# S7CAS-PLEIADES-CARTE-MERE_P02_DDR3.net
KiCad netlist of a schematic drawn in Altium Designer
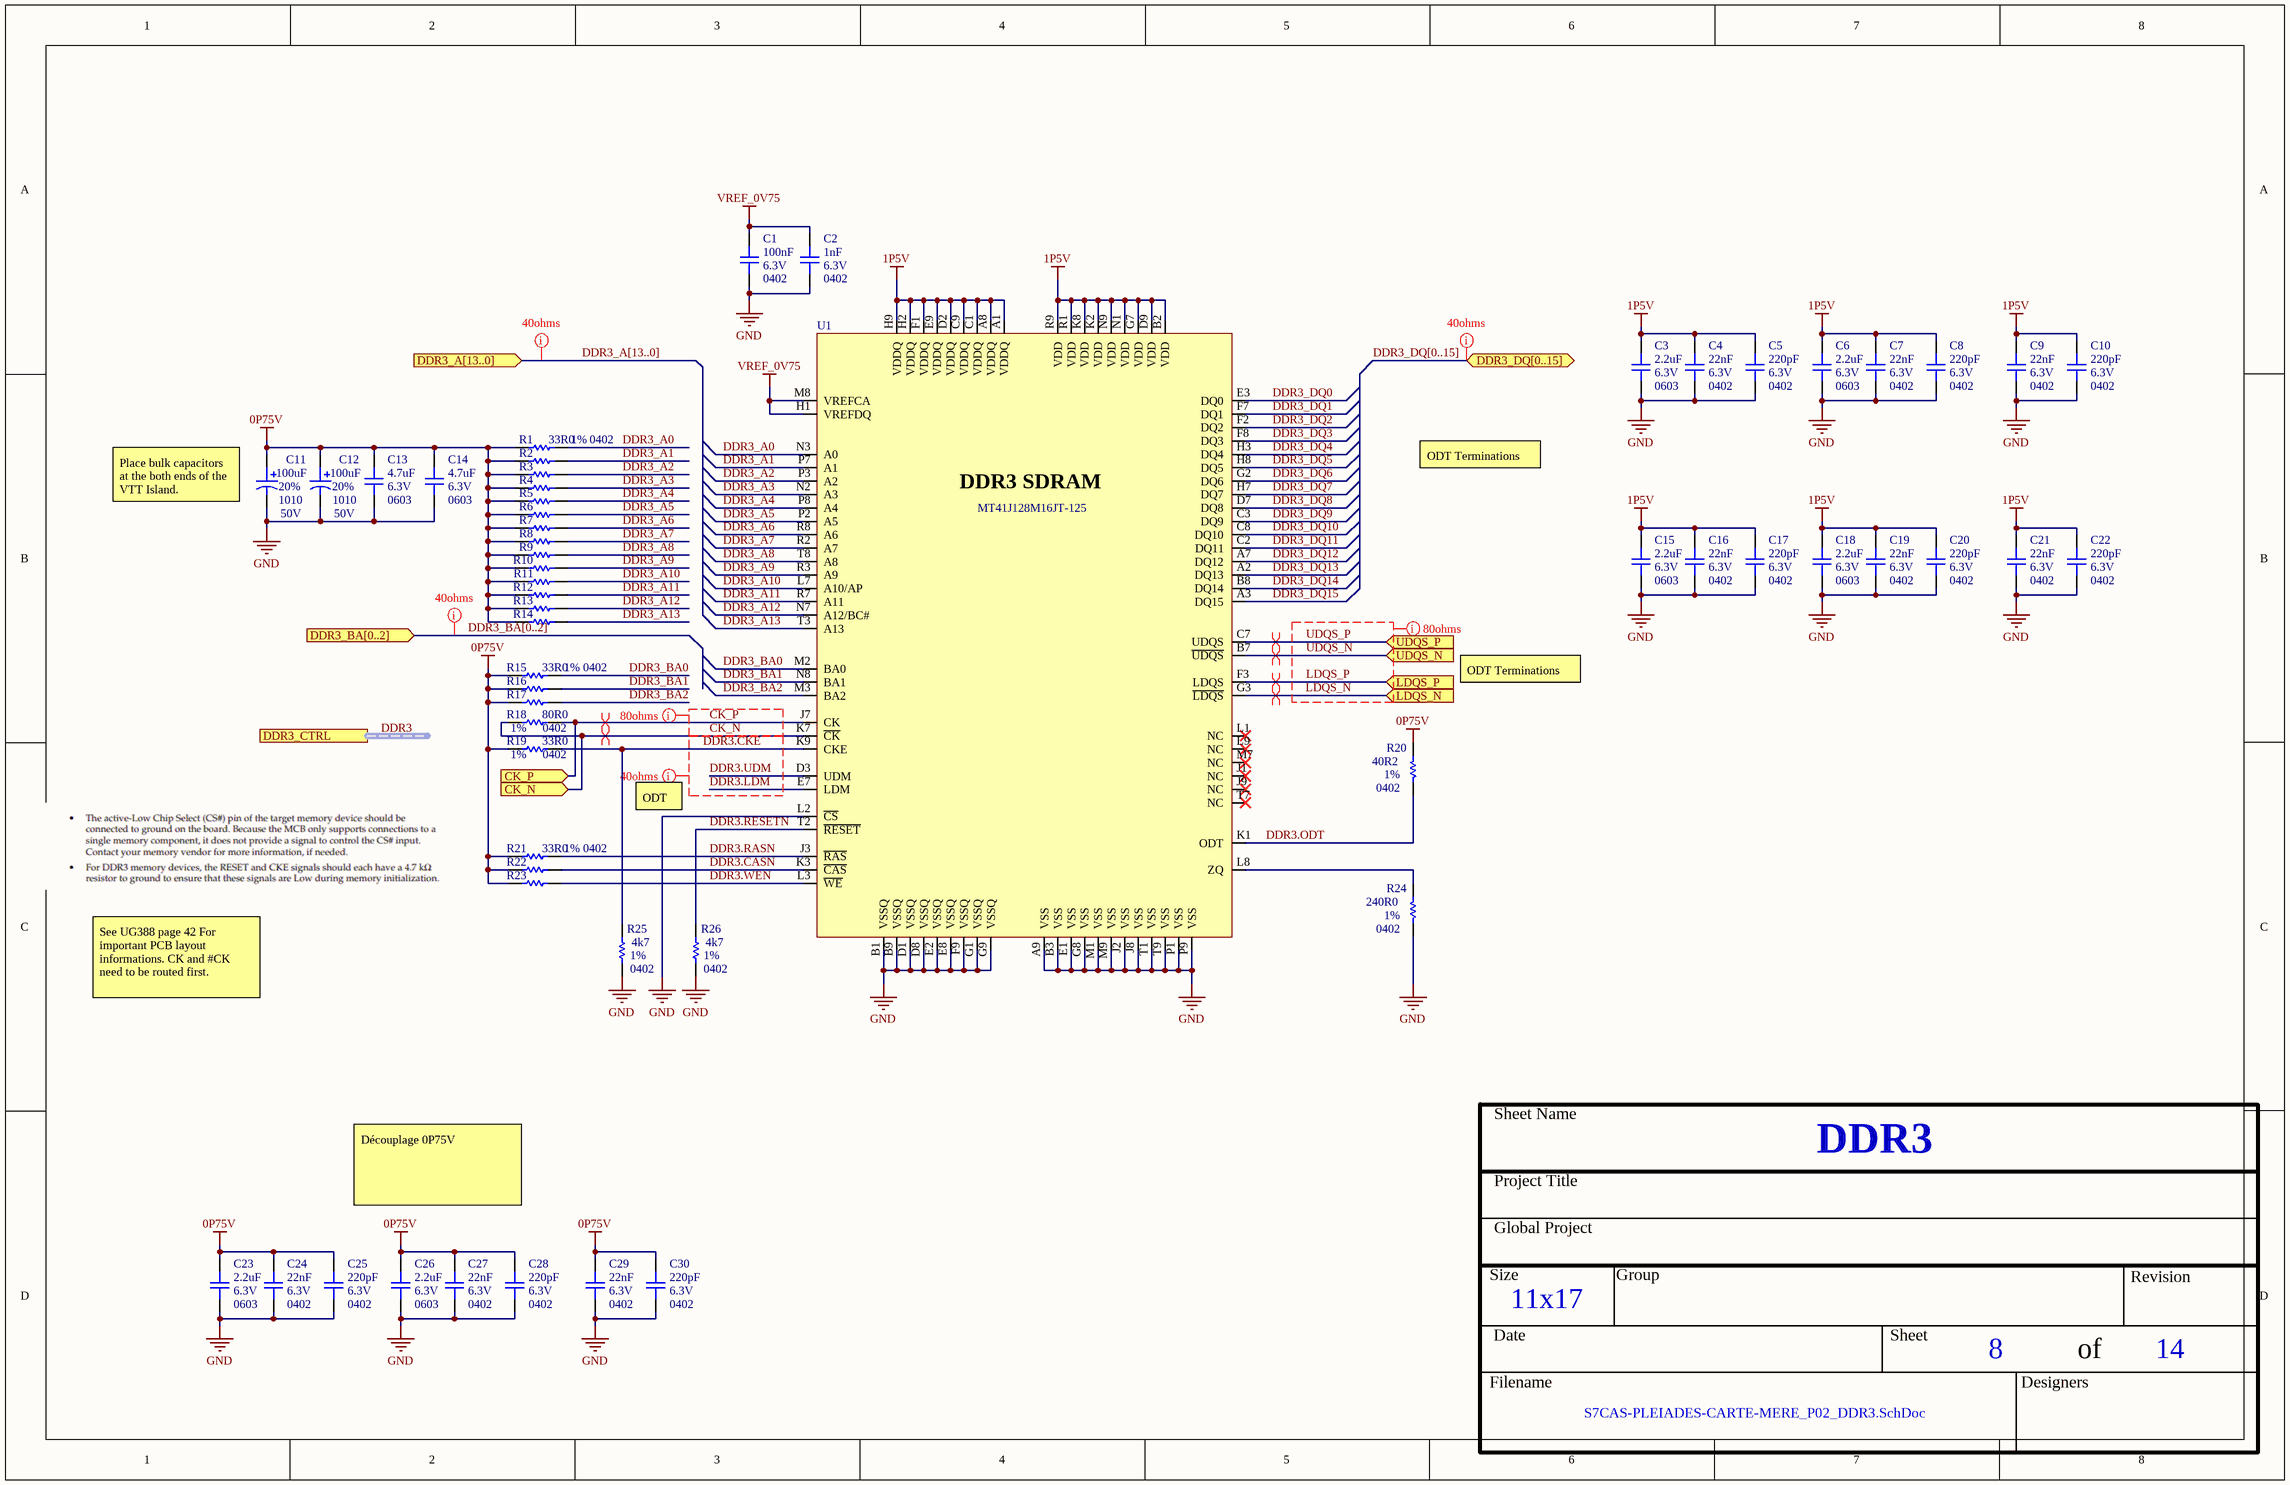
[diagram p0: S7CAS-PLEIADES-CARTE-MERE_P02_DDR3.SchDoc]

(export (version "E")
  (design (tool "Eeschema 10.0.6"))
  (components
    (comp (ref "C1")
      (value "100nF")
      (footprint "CAP_0402")
      (description "CAP - 0402")
      (fields
        (field (name "MFG") "Murata")
        (field (name "MFG PART NUMBER") "GRM022R60J104KE15")
        (field (name "VOLTAGE") "6.3V")
        (field (name "PACKAGE") "0402")
        (field (name "CREATEDBY") "Jonathan Bouchard")
      )
      (libsource (lib "S7CAS_Lib2019_REV1_00") (part "CAP - 0402"))
    )
    (comp (ref "C2")
      (value "1nF")
      (footprint "CAP_0402")
      (description "CAP - 0402")
      (fields
        (field (name "MFG") "Murata")
        (field (name "MFG PART NUMBER") "GRM022R60J104KE15")
        (field (name "VOLTAGE") "6.3V")
        (field (name "PACKAGE") "0402")
        (field (name "CREATEDBY") "Jonathan Bouchard")
      )
      (libsource (lib "S7CAS_Lib2019_REV1_00") (part "CAP - 0402"))
    )
    (comp (ref "C3")
      (value "2.2uF")
      (footprint "CAP_0603")
      (description "CAP - 0603")
      (fields
        (field (name "VOLTAGE") "6.3V")
        (field (name "PACKAGE") "0603")
        (field (name "CREATEDBY") "Jonathan Bouchard")
      )
      (libsource (lib "S7CAS_Lib2019_REV1_00") (part "CAP - 0603"))
    )
    (comp (ref "C4")
      (value "22nF")
      (footprint "CAP_0402")
      (description "CAP - 0402")
      (fields
        (field (name "MFG") "Murata")
        (field (name "MFG PART NUMBER") "GRM022R60J104KE15")
        (field (name "VOLTAGE") "6.3V")
        (field (name "PACKAGE") "0402")
        (field (name "CREATEDBY") "Jonathan Bouchard")
      )
      (libsource (lib "S7CAS_Lib2019_REV1_00") (part "CAP - 0402"))
    )
    (comp (ref "C5")
      (value "220pF")
      (footprint "CAP_0402")
      (description "CAP - 0402")
      (fields
        (field (name "MFG") "Murata")
        (field (name "MFG PART NUMBER") "GRM022R60J104KE15")
        (field (name "VOLTAGE") "6.3V")
        (field (name "PACKAGE") "0402")
        (field (name "CREATEDBY") "Jonathan Bouchard")
      )
      (libsource (lib "S7CAS_Lib2019_REV1_00") (part "CAP - 0402"))
    )
    (comp (ref "C6")
      (value "2.2uF")
      (footprint "CAP_0603")
      (description "CAP - 0603")
      (fields
        (field (name "VOLTAGE") "6.3V")
        (field (name "PACKAGE") "0603")
        (field (name "CREATEDBY") "Jonathan Bouchard")
      )
      (libsource (lib "S7CAS_Lib2019_REV1_00") (part "CAP - 0603"))
    )
    (comp (ref "C7")
      (value "22nF")
      (footprint "CAP_0402")
      (description "CAP - 0402")
      (fields
        (field (name "MFG") "Murata")
        (field (name "MFG PART NUMBER") "GRM022R60J104KE15")
        (field (name "VOLTAGE") "6.3V")
        (field (name "PACKAGE") "0402")
        (field (name "CREATEDBY") "Jonathan Bouchard")
      )
      (libsource (lib "S7CAS_Lib2019_REV1_00") (part "CAP - 0402"))
    )
    (comp (ref "C8")
      (value "220pF")
      (footprint "CAP_0402")
      (description "CAP - 0402")
      (fields
        (field (name "MFG") "Murata")
        (field (name "MFG PART NUMBER") "GRM022R60J104KE15")
        (field (name "VOLTAGE") "6.3V")
        (field (name "PACKAGE") "0402")
        (field (name "CREATEDBY") "Jonathan Bouchard")
      )
      (libsource (lib "S7CAS_Lib2019_REV1_00") (part "CAP - 0402"))
    )
    (comp (ref "C9")
      (value "22nF")
      (footprint "CAP_0402")
      (description "CAP - 0402")
      (fields
        (field (name "MFG") "Murata")
        (field (name "MFG PART NUMBER") "GRM022R60J104KE15")
        (field (name "VOLTAGE") "6.3V")
        (field (name "PACKAGE") "0402")
        (field (name "CREATEDBY") "Jonathan Bouchard")
      )
      (libsource (lib "S7CAS_Lib2019_REV1_00") (part "CAP - 0402"))
    )
    (comp (ref "C10")
      (value "220pF")
      (footprint "CAP_0402")
      (description "CAP - 0402")
      (fields
        (field (name "MFG") "Murata")
        (field (name "MFG PART NUMBER") "GRM022R60J104KE15")
        (field (name "VOLTAGE") "6.3V")
        (field (name "PACKAGE") "0402")
        (field (name "CREATEDBY") "Jonathan Bouchard")
      )
      (libsource (lib "S7CAS_Lib2019_REV1_00") (part "CAP - 0402"))
    )
    (comp (ref "C11")
      (value "100uF")
      (footprint "CAP_ALU_1010_vishay")
      (description "CAP - ALU 100uF 20% 50V - 1010")
      (fields
        (field (name "MFG") "Vishay Dale")
        (field (name "MFG PART NUMBER") "MAL215099101E3")
        (field (name "VOLTAGE") "50V")
        (field (name "PACKAGE") "1010")
        (field (name "PRECISION") "20%")
        (field (name "CREATEDBY") "Jonathan Bouchard")
      )
      (libsource (lib "S7CAS_Lib2019_REV1_00") (part "CAP_ALU_MAL215099101E3"))
    )
    (comp (ref "C12")
      (value "100uF")
      (footprint "CAP_ALU_1010_vishay")
      (description "CAP - ALU 100uF 20% 50V - 1010")
      (fields
        (field (name "MFG") "Vishay Dale")
        (field (name "MFG PART NUMBER") "MAL215099101E3")
        (field (name "VOLTAGE") "50V")
        (field (name "PACKAGE") "1010")
        (field (name "PRECISION") "20%")
        (field (name "CREATEDBY") "Jonathan Bouchard")
      )
      (libsource (lib "S7CAS_Lib2019_REV1_00") (part "CAP_ALU_MAL215099101E3"))
    )
    (comp (ref "C13")
      (value "4.7uF")
      (footprint "CAP_0603")
      (description "CAP - 0603")
      (fields
        (field (name "VOLTAGE") "6.3V")
        (field (name "PACKAGE") "0603")
        (field (name "CREATEDBY") "Jonathan Bouchard")
      )
      (libsource (lib "S7CAS_Lib2019_REV1_00") (part "CAP - 0603"))
    )
    (comp (ref "C14")
      (value "4.7uF")
      (footprint "CAP_0603")
      (description "CAP - 0603")
      (fields
        (field (name "VOLTAGE") "6.3V")
        (field (name "PACKAGE") "0603")
        (field (name "CREATEDBY") "Jonathan Bouchard")
      )
      (libsource (lib "S7CAS_Lib2019_REV1_00") (part "CAP - 0603"))
    )
    (comp (ref "C15")
      (value "2.2uF")
      (footprint "CAP_0603")
      (description "CAP - 0603")
      (fields
        (field (name "VOLTAGE") "6.3V")
        (field (name "PACKAGE") "0603")
        (field (name "CREATEDBY") "Jonathan Bouchard")
      )
      (libsource (lib "S7CAS_Lib2019_REV1_00") (part "CAP - 0603"))
    )
    (comp (ref "C16")
      (value "22nF")
      (footprint "CAP_0402")
      (description "CAP - 0402")
      (fields
        (field (name "MFG") "Murata")
        (field (name "MFG PART NUMBER") "GRM022R60J104KE15")
        (field (name "VOLTAGE") "6.3V")
        (field (name "PACKAGE") "0402")
        (field (name "CREATEDBY") "Jonathan Bouchard")
      )
      (libsource (lib "S7CAS_Lib2019_REV1_00") (part "CAP - 0402"))
    )
    (comp (ref "C17")
      (value "220pF")
      (footprint "CAP_0402")
      (description "CAP - 0402")
      (fields
        (field (name "MFG") "Murata")
        (field (name "MFG PART NUMBER") "GRM022R60J104KE15")
        (field (name "VOLTAGE") "6.3V")
        (field (name "PACKAGE") "0402")
        (field (name "CREATEDBY") "Jonathan Bouchard")
      )
      (libsource (lib "S7CAS_Lib2019_REV1_00") (part "CAP - 0402"))
    )
    (comp (ref "C18")
      (value "2.2uF")
      (footprint "CAP_0603")
      (description "CAP - 0603")
      (fields
        (field (name "VOLTAGE") "6.3V")
        (field (name "PACKAGE") "0603")
        (field (name "CREATEDBY") "Jonathan Bouchard")
      )
      (libsource (lib "S7CAS_Lib2019_REV1_00") (part "CAP - 0603"))
    )
    (comp (ref "C19")
      (value "22nF")
      (footprint "CAP_0402")
      (description "CAP - 0402")
      (fields
        (field (name "MFG") "Murata")
        (field (name "MFG PART NUMBER") "GRM022R60J104KE15")
        (field (name "VOLTAGE") "6.3V")
        (field (name "PACKAGE") "0402")
        (field (name "CREATEDBY") "Jonathan Bouchard")
      )
      (libsource (lib "S7CAS_Lib2019_REV1_00") (part "CAP - 0402"))
    )
    (comp (ref "C20")
      (value "220pF")
      (footprint "CAP_0402")
      (description "CAP - 0402")
      (fields
        (field (name "MFG") "Murata")
        (field (name "MFG PART NUMBER") "GRM022R60J104KE15")
        (field (name "VOLTAGE") "6.3V")
        (field (name "PACKAGE") "0402")
        (field (name "CREATEDBY") "Jonathan Bouchard")
      )
      (libsource (lib "S7CAS_Lib2019_REV1_00") (part "CAP - 0402"))
    )
    (comp (ref "C21")
      (value "22nF")
      (footprint "CAP_0402")
      (description "CAP - 0402")
      (fields
        (field (name "MFG") "Murata")
        (field (name "MFG PART NUMBER") "GRM022R60J104KE15")
        (field (name "VOLTAGE") "6.3V")
        (field (name "PACKAGE") "0402")
        (field (name "CREATEDBY") "Jonathan Bouchard")
      )
      (libsource (lib "S7CAS_Lib2019_REV1_00") (part "CAP - 0402"))
    )
    (comp (ref "C22")
      (value "220pF")
      (footprint "CAP_0402")
      (description "CAP - 0402")
      (fields
        (field (name "MFG") "Murata")
        (field (name "MFG PART NUMBER") "GRM022R60J104KE15")
        (field (name "VOLTAGE") "6.3V")
        (field (name "PACKAGE") "0402")
        (field (name "CREATEDBY") "Jonathan Bouchard")
      )
      (libsource (lib "S7CAS_Lib2019_REV1_00") (part "CAP - 0402"))
    )
    (comp (ref "C23")
      (value "2.2uF")
      (footprint "CAP_0603")
      (description "CAP - 0603")
      (fields
        (field (name "VOLTAGE") "6.3V")
        (field (name "PACKAGE") "0603")
        (field (name "CREATEDBY") "Jonathan Bouchard")
      )
      (libsource (lib "S7CAS_Lib2019_REV1_00") (part "CAP - 0603"))
    )
    (comp (ref "C24")
      (value "22nF")
      (footprint "CAP_0402")
      (description "CAP - 0402")
      (fields
        (field (name "MFG") "Murata")
        (field (name "MFG PART NUMBER") "GRM022R60J104KE15")
        (field (name "VOLTAGE") "6.3V")
        (field (name "PACKAGE") "0402")
        (field (name "CREATEDBY") "Jonathan Bouchard")
      )
      (libsource (lib "S7CAS_Lib2019_REV1_00") (part "CAP - 0402"))
    )
    (comp (ref "C25")
      (value "220pF")
      (footprint "CAP_0402")
      (description "CAP - 0402")
      (fields
        (field (name "MFG") "Murata")
        (field (name "MFG PART NUMBER") "GRM022R60J104KE15")
        (field (name "VOLTAGE") "6.3V")
        (field (name "PACKAGE") "0402")
        (field (name "CREATEDBY") "Jonathan Bouchard")
      )
      (libsource (lib "S7CAS_Lib2019_REV1_00") (part "CAP - 0402"))
    )
    (comp (ref "C26")
      (value "2.2uF")
      (footprint "CAP_0603")
      (description "CAP - 0603")
      (fields
        (field (name "VOLTAGE") "6.3V")
        (field (name "PACKAGE") "0603")
        (field (name "CREATEDBY") "Jonathan Bouchard")
      )
      (libsource (lib "S7CAS_Lib2019_REV1_00") (part "CAP - 0603"))
    )
    (comp (ref "C27")
      (value "22nF")
      (footprint "CAP_0402")
      (description "CAP - 0402")
      (fields
        (field (name "MFG") "Murata")
        (field (name "MFG PART NUMBER") "GRM022R60J104KE15")
        (field (name "VOLTAGE") "6.3V")
        (field (name "PACKAGE") "0402")
        (field (name "CREATEDBY") "Jonathan Bouchard")
      )
      (libsource (lib "S7CAS_Lib2019_REV1_00") (part "CAP - 0402"))
    )
    (comp (ref "C28")
      (value "220pF")
      (footprint "CAP_0402")
      (description "CAP - 0402")
      (fields
        (field (name "MFG") "Murata")
        (field (name "MFG PART NUMBER") "GRM022R60J104KE15")
        (field (name "VOLTAGE") "6.3V")
        (field (name "PACKAGE") "0402")
        (field (name "CREATEDBY") "Jonathan Bouchard")
      )
      (libsource (lib "S7CAS_Lib2019_REV1_00") (part "CAP - 0402"))
    )
    (comp (ref "C29")
      (value "22nF")
      (footprint "CAP_0402")
      (description "CAP - 0402")
      (fields
        (field (name "MFG") "Murata")
        (field (name "MFG PART NUMBER") "GRM022R60J104KE15")
        (field (name "VOLTAGE") "6.3V")
        (field (name "PACKAGE") "0402")
        (field (name "CREATEDBY") "Jonathan Bouchard")
      )
      (libsource (lib "S7CAS_Lib2019_REV1_00") (part "CAP - 0402"))
    )
    (comp (ref "C30")
      (value "220pF")
      (footprint "CAP_0402")
      (description "CAP - 0402")
      (fields
        (field (name "MFG") "Murata")
        (field (name "MFG PART NUMBER") "GRM022R60J104KE15")
        (field (name "VOLTAGE") "6.3V")
        (field (name "PACKAGE") "0402")
        (field (name "CREATEDBY") "Jonathan Bouchard")
      )
      (libsource (lib "S7CAS_Lib2019_REV1_00") (part "CAP - 0402"))
    )
    (comp (ref "R1")
      (value "33R0")
      (footprint "RES_0402")
      (description "RES - 0402")
      (fields
        (field (name "VOLTAGE") "50V")
        (field (name "POWER") "1/16W")
        (field (name "PACKAGE") "0402")
        (field (name "PRECISION") "1%")
        (field (name "CREATEDBY") "Jonathan Bouchard")
      )
      (libsource (lib "S7CAS_Lib2019_REV1_00") (part "RES - 0402"))
    )
    (comp (ref "R2")
      (value "RES - 0402")
      (footprint "RES_0402")
      (fields
        (field (name "VOLTAGE") "50V")
        (field (name "POWER") "1/16W")
        (field (name "CREATEDBY") "Jonathan Bouchard")
      )
      (libsource (lib "S7CAS_Lib2019_REV1_00") (part "RES - 0402"))
    )
    (comp (ref "R3")
      (value "RES - 0402")
      (footprint "RES_0402")
      (fields
        (field (name "VOLTAGE") "50V")
        (field (name "POWER") "1/16W")
        (field (name "CREATEDBY") "Jonathan Bouchard")
      )
      (libsource (lib "S7CAS_Lib2019_REV1_00") (part "RES - 0402"))
    )
    (comp (ref "R4")
      (value "RES - 0402")
      (footprint "RES_0402")
      (fields
        (field (name "VOLTAGE") "50V")
        (field (name "POWER") "1/16W")
        (field (name "CREATEDBY") "Jonathan Bouchard")
      )
      (libsource (lib "S7CAS_Lib2019_REV1_00") (part "RES - 0402"))
    )
    (comp (ref "R5")
      (value "RES - 0402")
      (footprint "RES_0402")
      (fields
        (field (name "VOLTAGE") "50V")
        (field (name "POWER") "1/16W")
        (field (name "CREATEDBY") "Jonathan Bouchard")
      )
      (libsource (lib "S7CAS_Lib2019_REV1_00") (part "RES - 0402"))
    )
    (comp (ref "R6")
      (value "RES - 0402")
      (footprint "RES_0402")
      (fields
        (field (name "VOLTAGE") "50V")
        (field (name "POWER") "1/16W")
        (field (name "CREATEDBY") "Jonathan Bouchard")
      )
      (libsource (lib "S7CAS_Lib2019_REV1_00") (part "RES - 0402"))
    )
    (comp (ref "R7")
      (value "RES - 0402")
      (footprint "RES_0402")
      (fields
        (field (name "VOLTAGE") "50V")
        (field (name "POWER") "1/16W")
        (field (name "CREATEDBY") "Jonathan Bouchard")
      )
      (libsource (lib "S7CAS_Lib2019_REV1_00") (part "RES - 0402"))
    )
    (comp (ref "R8")
      (value "RES - 0402")
      (footprint "RES_0402")
      (fields
        (field (name "VOLTAGE") "50V")
        (field (name "POWER") "1/16W")
        (field (name "CREATEDBY") "Jonathan Bouchard")
      )
      (libsource (lib "S7CAS_Lib2019_REV1_00") (part "RES - 0402"))
    )
    (comp (ref "R9")
      (value "RES - 0402")
      (footprint "RES_0402")
      (fields
        (field (name "VOLTAGE") "50V")
        (field (name "POWER") "1/16W")
        (field (name "CREATEDBY") "Jonathan Bouchard")
      )
      (libsource (lib "S7CAS_Lib2019_REV1_00") (part "RES - 0402"))
    )
    (comp (ref "R10")
      (value "RES - 0402")
      (footprint "RES_0402")
      (fields
        (field (name "VOLTAGE") "50V")
        (field (name "POWER") "1/16W")
        (field (name "CREATEDBY") "Jonathan Bouchard")
      )
      (libsource (lib "S7CAS_Lib2019_REV1_00") (part "RES - 0402"))
    )
    (comp (ref "R11")
      (value "RES - 0402")
      (footprint "RES_0402")
      (fields
        (field (name "VOLTAGE") "50V")
        (field (name "POWER") "1/16W")
        (field (name "CREATEDBY") "Jonathan Bouchard")
      )
      (libsource (lib "S7CAS_Lib2019_REV1_00") (part "RES - 0402"))
    )
    (comp (ref "R12")
      (value "RES - 0402")
      (footprint "RES_0402")
      (fields
        (field (name "VOLTAGE") "50V")
        (field (name "POWER") "1/16W")
        (field (name "CREATEDBY") "Jonathan Bouchard")
      )
      (libsource (lib "S7CAS_Lib2019_REV1_00") (part "RES - 0402"))
    )
    (comp (ref "R13")
      (value "RES - 0402")
      (footprint "RES_0402")
      (fields
        (field (name "VOLTAGE") "50V")
        (field (name "POWER") "1/16W")
        (field (name "CREATEDBY") "Jonathan Bouchard")
      )
      (libsource (lib "S7CAS_Lib2019_REV1_00") (part "RES - 0402"))
    )
    (comp (ref "R14")
      (value "RES - 0402")
      (footprint "RES_0402")
      (fields
        (field (name "VOLTAGE") "50V")
        (field (name "POWER") "1/16W")
        (field (name "CREATEDBY") "Jonathan Bouchard")
      )
      (libsource (lib "S7CAS_Lib2019_REV1_00") (part "RES - 0402"))
    )
    (comp (ref "R15")
      (value "33R0")
      (footprint "RES_0402")
      (description "RES - 0402")
      (fields
        (field (name "VOLTAGE") "50V")
        (field (name "POWER") "1/16W")
        (field (name "PACKAGE") "0402")
        (field (name "PRECISION") "1%")
        (field (name "CREATEDBY") "Jonathan Bouchard")
      )
      (libsource (lib "S7CAS_Lib2019_REV1_00") (part "RES - 0402"))
    )
    (comp (ref "R16")
      (value "RES - 0402")
      (footprint "RES_0402")
      (fields
        (field (name "VOLTAGE") "50V")
        (field (name "POWER") "1/16W")
        (field (name "CREATEDBY") "Jonathan Bouchard")
      )
      (libsource (lib "S7CAS_Lib2019_REV1_00") (part "RES - 0402"))
    )
    (comp (ref "R17")
      (value "RES - 0402")
      (footprint "RES_0402")
      (fields
        (field (name "VOLTAGE") "50V")
        (field (name "POWER") "1/16W")
        (field (name "CREATEDBY") "Jonathan Bouchard")
      )
      (libsource (lib "S7CAS_Lib2019_REV1_00") (part "RES - 0402"))
    )
    (comp (ref "R18")
      (value "80R0")
      (footprint "RES_0402")
      (description "RES - 0402")
      (fields
        (field (name "VOLTAGE") "50V")
        (field (name "POWER") "1/16W")
        (field (name "PACKAGE") "0402")
        (field (name "PRECISION") "1%")
        (field (name "CREATEDBY") "Jonathan Bouchard")
      )
      (libsource (lib "S7CAS_Lib2019_REV1_00") (part "RES - 0402"))
    )
    (comp (ref "R19")
      (value "33R0")
      (footprint "RES_0402")
      (description "RES - 0402")
      (fields
        (field (name "VOLTAGE") "50V")
        (field (name "POWER") "1/16W")
        (field (name "PACKAGE") "0402")
        (field (name "PRECISION") "1%")
        (field (name "CREATEDBY") "Jonathan Bouchard")
      )
      (libsource (lib "S7CAS_Lib2019_REV1_00") (part "RES - 0402"))
    )
    (comp (ref "R20")
      (value "40R2")
      (footprint "RES_0402")
      (description "RES - 0402")
      (fields
        (field (name "VOLTAGE") "50V")
        (field (name "POWER") "1/16W")
        (field (name "PACKAGE") "0402")
        (field (name "PRECISION") "1%")
        (field (name "CREATEDBY") "Jonathan Bouchard")
      )
      (libsource (lib "S7CAS_Lib2019_REV1_00") (part "RES - 0402"))
    )
    (comp (ref "R21")
      (value "33R0")
      (footprint "RES_0402")
      (description "RES - 0402")
      (fields
        (field (name "VOLTAGE") "50V")
        (field (name "POWER") "1/16W")
        (field (name "PACKAGE") "0402")
        (field (name "PRECISION") "1%")
        (field (name "CREATEDBY") "Jonathan Bouchard")
      )
      (libsource (lib "S7CAS_Lib2019_REV1_00") (part "RES - 0402"))
    )
    (comp (ref "R22")
      (value "RES - 0402")
      (footprint "RES_0402")
      (fields
        (field (name "VOLTAGE") "50V")
        (field (name "POWER") "1/16W")
        (field (name "CREATEDBY") "Jonathan Bouchard")
      )
      (libsource (lib "S7CAS_Lib2019_REV1_00") (part "RES - 0402"))
    )
    (comp (ref "R23")
      (value "RES - 0402")
      (footprint "RES_0402")
      (fields
        (field (name "VOLTAGE") "50V")
        (field (name "POWER") "1/16W")
        (field (name "CREATEDBY") "Jonathan Bouchard")
      )
      (libsource (lib "S7CAS_Lib2019_REV1_00") (part "RES - 0402"))
    )
    (comp (ref "R24")
      (value "240R0")
      (footprint "RES_0402")
      (description "RES - 0402")
      (fields
        (field (name "VOLTAGE") "50V")
        (field (name "POWER") "1/16W")
        (field (name "PACKAGE") "0402")
        (field (name "PRECISION") "1%")
        (field (name "CREATEDBY") "Jonathan Bouchard")
      )
      (libsource (lib "S7CAS_Lib2019_REV1_00") (part "RES - 0402"))
    )
    (comp (ref "R25")
      (value "4k7")
      (footprint "RES_0402")
      (description "RES - 0402")
      (fields
        (field (name "VOLTAGE") "50V")
        (field (name "POWER") "1/16W")
        (field (name "PACKAGE") "0402")
        (field (name "PRECISION") "1%")
        (field (name "CREATEDBY") "Jonathan Bouchard")
      )
      (libsource (lib "S7CAS_Lib2019_REV1_00") (part "RES - 0402"))
    )
    (comp (ref "R26")
      (value "4k7")
      (footprint "RES_0402")
      (description "RES - 0402")
      (fields
        (field (name "VOLTAGE") "50V")
        (field (name "POWER") "1/16W")
        (field (name "PACKAGE") "0402")
        (field (name "PRECISION") "1%")
        (field (name "CREATEDBY") "Jonathan Bouchard")
      )
      (libsource (lib "S7CAS_Lib2019_REV1_00") (part "RES - 0402"))
    )
    (comp (ref "U1")
      (value "MT41J128M16JT-125")
      (footprint "MEM_DDR3_MT41J128M16JT-125")
      (description "MEM - DDR3 SDRAM 2GBIT 800MHZ - TFBGA-96")
      (fields
        (field (name "VOLTAGE") "1.425 V ~ 1.575 V")
        (field (name "MFG") "Micrel")
        (field (name "CREATEDBY") "Jonathan Bouchard")
      )
      (libsource (lib "S7CAS_Lib2019_REV1_00") (part "MEM_DDR3_MT41J128M16JT-125{colon}K TR"))
    )
  )
  (nets
    (net (code "2") (name "/CK_N") (class "Default")
      (node (ref "R18") (pin "2") (pinfunction "2_2") (pintype "passive"))
      (node (ref "U1") (pin "K7") (pinfunction "CK_K7") (pintype "passive"))
    )
    (net (code "3") (name "/CK_P") (class "Default")
      (node (ref "R18") (pin "1") (pinfunction "1_1") (pintype "passive"))
      (node (ref "U1") (pin "J7") (pinfunction "CK_J7") (pintype "passive"))
    )
    (net (code "4") (name "/DDR3.CASN") (class "Default")
      (node (ref "R22") (pin "1") (pinfunction "1_1") (pintype "passive"))
      (node (ref "U1") (pin "K3") (pinfunction "CAS_K3") (pintype "passive"))
    )
    (net (code "5") (name "/DDR3.CKE") (class "Default")
      (node (ref "R19") (pin "1") (pinfunction "1_1") (pintype "passive"))
      (node (ref "R25") (pin "2") (pinfunction "2_2") (pintype "passive"))
      (node (ref "U1") (pin "K9") (pinfunction "CKE_K9") (pintype "passive"))
    )
    (net (code "6") (name "/DDR3.LDM") (class "Default")
      (node (ref "U1") (pin "E7") (pinfunction "LDM_E7") (pintype "power_in"))
    )
    (net (code "7") (name "/DDR3.ODT") (class "Default")
      (node (ref "R20") (pin "1") (pinfunction "1_1") (pintype "passive"))
      (node (ref "U1") (pin "K1") (pinfunction "ODT_K1") (pintype "passive"))
    )
    (net (code "8") (name "/DDR3.RASN") (class "Default")
      (node (ref "R21") (pin "1") (pinfunction "1_1") (pintype "passive"))
      (node (ref "U1") (pin "J3") (pinfunction "RAS_J3") (pintype "passive"))
    )
    (net (code "9") (name "/DDR3.RESETN") (class "Default")
      (node (ref "R26") (pin "2") (pinfunction "2_2") (pintype "passive"))
      (node (ref "U1") (pin "T2") (pinfunction "RESET_T2") (pintype "passive"))
    )
    (net (code "10") (name "/DDR3.UDM") (class "Default")
      (node (ref "U1") (pin "D3") (pinfunction "UDM_D3") (pintype "power_in"))
    )
    (net (code "11") (name "/DDR3.WEN") (class "Default")
      (node (ref "R23") (pin "1") (pinfunction "1_1") (pintype "passive"))
      (node (ref "U1") (pin "L3") (pinfunction "WE_L3") (pintype "passive"))
    )
    (net (code "12") (name "/DDR3_A0") (class "Default")
      (node (ref "R1") (pin "1") (pinfunction "1_1") (pintype "passive"))
      (node (ref "U1") (pin "N3") (pinfunction "A0_N3") (pintype "passive"))
    )
    (net (code "13") (name "/DDR3_A1") (class "Default")
      (node (ref "R2") (pin "1") (pinfunction "1_1") (pintype "passive"))
      (node (ref "U1") (pin "P7") (pinfunction "A1_P7") (pintype "passive"))
    )
    (net (code "14") (name "/DDR3_A2") (class "Default")
      (node (ref "R3") (pin "1") (pinfunction "1_1") (pintype "passive"))
      (node (ref "U1") (pin "P3") (pinfunction "A2_P3") (pintype "passive"))
    )
    (net (code "15") (name "/DDR3_A3") (class "Default")
      (node (ref "R4") (pin "1") (pinfunction "1_1") (pintype "passive"))
      (node (ref "U1") (pin "N2") (pinfunction "A3_N2") (pintype "passive"))
    )
    (net (code "16") (name "/DDR3_A4") (class "Default")
      (node (ref "R5") (pin "1") (pinfunction "1_1") (pintype "passive"))
      (node (ref "U1") (pin "P8") (pinfunction "A4_P8") (pintype "passive"))
    )
    (net (code "17") (name "/DDR3_A5") (class "Default")
      (node (ref "R6") (pin "1") (pinfunction "1_1") (pintype "passive"))
      (node (ref "U1") (pin "P2") (pinfunction "A5_P2") (pintype "passive"))
    )
    (net (code "18") (name "/DDR3_A6") (class "Default")
      (node (ref "R7") (pin "1") (pinfunction "1_1") (pintype "passive"))
      (node (ref "U1") (pin "R8") (pinfunction "A6_R8") (pintype "passive"))
    )
    (net (code "19") (name "/DDR3_A7") (class "Default")
      (node (ref "R8") (pin "1") (pinfunction "1_1") (pintype "passive"))
      (node (ref "U1") (pin "R2") (pinfunction "A7_R2") (pintype "passive"))
    )
    (net (code "20") (name "/DDR3_A8") (class "Default")
      (node (ref "R9") (pin "1") (pinfunction "1_1") (pintype "passive"))
      (node (ref "U1") (pin "T8") (pinfunction "A8_T8") (pintype "passive"))
    )
    (net (code "21") (name "/DDR3_A9") (class "Default")
      (node (ref "R10") (pin "1") (pinfunction "1_1") (pintype "passive"))
      (node (ref "U1") (pin "R3") (pinfunction "A9_R3") (pintype "passive"))
    )
    (net (code "22") (name "/DDR3_A10") (class "Default")
      (node (ref "R11") (pin "1") (pinfunction "1_1") (pintype "passive"))
      (node (ref "U1") (pin "L7") (pinfunction "A10/AP_L7") (pintype "passive"))
    )
    (net (code "23") (name "/DDR3_A11") (class "Default")
      (node (ref "R12") (pin "1") (pinfunction "1_1") (pintype "passive"))
      (node (ref "U1") (pin "R7") (pinfunction "A11_R7") (pintype "passive"))
    )
    (net (code "24") (name "/DDR3_A12") (class "Default")
      (node (ref "R13") (pin "1") (pinfunction "1_1") (pintype "passive"))
      (node (ref "U1") (pin "N7") (pinfunction "A12/BC#_N7") (pintype "passive"))
    )
    (net (code "25") (name "/DDR3_A13") (class "Default")
      (node (ref "R14") (pin "1") (pinfunction "1_1") (pintype "passive"))
      (node (ref "U1") (pin "T3") (pinfunction "A13_T3") (pintype "passive"))
    )
    (net (code "27") (name "/DDR3_BA0") (class "Default")
      (node (ref "R15") (pin "1") (pinfunction "1_1") (pintype "passive"))
      (node (ref "U1") (pin "M2") (pinfunction "BA0_M2") (pintype "passive"))
    )
    (net (code "28") (name "/DDR3_BA1") (class "Default")
      (node (ref "R16") (pin "1") (pinfunction "1_1") (pintype "passive"))
      (node (ref "U1") (pin "N8") (pinfunction "BA1_N8") (pintype "passive"))
    )
    (net (code "29") (name "/DDR3_BA2") (class "Default")
      (node (ref "R17") (pin "1") (pinfunction "1_1") (pintype "passive"))
      (node (ref "U1") (pin "M3") (pinfunction "BA2_M3") (pintype "passive"))
    )
    (net (code "31") (name "/DDR3_DQ0") (class "Default")
      (node (ref "U1") (pin "E3") (pinfunction "DQ0_E3") (pintype "passive"))
    )
    (net (code "32") (name "/DDR3_DQ1") (class "Default")
      (node (ref "U1") (pin "F7") (pinfunction "DQ1_F7") (pintype "passive"))
    )
    (net (code "33") (name "/DDR3_DQ2") (class "Default")
      (node (ref "U1") (pin "F2") (pinfunction "DQ2_F2") (pintype "passive"))
    )
    (net (code "34") (name "/DDR3_DQ3") (class "Default")
      (node (ref "U1") (pin "F8") (pinfunction "DQ3_F8") (pintype "passive"))
    )
    (net (code "35") (name "/DDR3_DQ4") (class "Default")
      (node (ref "U1") (pin "H3") (pinfunction "DQ4_H3") (pintype "passive"))
    )
    (net (code "36") (name "/DDR3_DQ5") (class "Default")
      (node (ref "U1") (pin "H8") (pinfunction "DQ5_H8") (pintype "passive"))
    )
    (net (code "37") (name "/DDR3_DQ6") (class "Default")
      (node (ref "U1") (pin "G2") (pinfunction "DQ6_G2") (pintype "passive"))
    )
    (net (code "38") (name "/DDR3_DQ7") (class "Default")
      (node (ref "U1") (pin "H7") (pinfunction "DQ7_H7") (pintype "passive"))
    )
    (net (code "39") (name "/DDR3_DQ8") (class "Default")
      (node (ref "U1") (pin "D7") (pinfunction "DQ8_D7") (pintype "passive"))
    )
    (net (code "40") (name "/DDR3_DQ9") (class "Default")
      (node (ref "U1") (pin "C3") (pinfunction "DQ9_C3") (pintype "passive"))
    )
    (net (code "41") (name "/DDR3_DQ10") (class "Default")
      (node (ref "U1") (pin "C8") (pinfunction "DQ10_C8") (pintype "passive"))
    )
    (net (code "42") (name "/DDR3_DQ11") (class "Default")
      (node (ref "U1") (pin "C2") (pinfunction "DQ11_C2") (pintype "passive"))
    )
    (net (code "43") (name "/DDR3_DQ12") (class "Default")
      (node (ref "U1") (pin "A7") (pinfunction "DQ12_A7") (pintype "passive"))
    )
    (net (code "44") (name "/DDR3_DQ13") (class "Default")
      (node (ref "U1") (pin "A2") (pinfunction "DQ13_A2") (pintype "passive"))
    )
    (net (code "45") (name "/DDR3_DQ14") (class "Default")
      (node (ref "U1") (pin "B8") (pinfunction "DQ14_B8") (pintype "passive"))
    )
    (net (code "46") (name "/DDR3_DQ15") (class "Default")
      (node (ref "U1") (pin "A3") (pinfunction "DQ15_A3") (pintype "passive"))
    )
    (net (code "48") (name "/LDQS_N") (class "Default")
      (node (ref "U1") (pin "G3") (pinfunction "LDQS_G3") (pintype "passive"))
    )
    (net (code "49") (name "/LDQS_P") (class "Default")
      (node (ref "U1") (pin "F3") (pinfunction "LDQS_F3") (pintype "passive"))
    )
    (net (code "50") (name "/UDQS_N") (class "Default")
      (node (ref "U1") (pin "B7") (pinfunction "UDQS_B7") (pintype "passive"))
    )
    (net (code "51") (name "/UDQS_P") (class "Default")
      (node (ref "U1") (pin "C7") (pinfunction "UDQS_C7") (pintype "passive"))
    )
    (net (code "53") (name "0P75V") (class "Default")
      (node (ref "C11") (pin "1") (pinfunction "1_1") (pintype "passive"))
      (node (ref "C12") (pin "1") (pinfunction "1_1") (pintype "passive"))
      (node (ref "C13") (pin "2") (pinfunction "2_2") (pintype "passive"))
      (node (ref "C14") (pin "2") (pinfunction "2_2") (pintype "passive"))
      (node (ref "C23") (pin "2") (pinfunction "2_2") (pintype "passive"))
      (node (ref "C24") (pin "2") (pinfunction "2_2") (pintype "passive"))
      (node (ref "C25") (pin "2") (pinfunction "2_2") (pintype "passive"))
      (node (ref "C26") (pin "2") (pinfunction "2_2") (pintype "passive"))
      (node (ref "C27") (pin "2") (pinfunction "2_2") (pintype "passive"))
      (node (ref "C28") (pin "2") (pinfunction "2_2") (pintype "passive"))
      (node (ref "C29") (pin "2") (pinfunction "2_2") (pintype "passive"))
      (node (ref "C30") (pin "2") (pinfunction "2_2") (pintype "passive"))
      (node (ref "R1") (pin "2") (pinfunction "2_2") (pintype "passive"))
      (node (ref "R10") (pin "2") (pinfunction "2_2") (pintype "passive"))
      (node (ref "R11") (pin "2") (pinfunction "2_2") (pintype "passive"))
      (node (ref "R12") (pin "2") (pinfunction "2_2") (pintype "passive"))
      (node (ref "R13") (pin "2") (pinfunction "2_2") (pintype "passive"))
      (node (ref "R14") (pin "2") (pinfunction "2_2") (pintype "passive"))
      (node (ref "R15") (pin "2") (pinfunction "2_2") (pintype "passive"))
      (node (ref "R16") (pin "2") (pinfunction "2_2") (pintype "passive"))
      (node (ref "R17") (pin "2") (pinfunction "2_2") (pintype "passive"))
      (node (ref "R19") (pin "2") (pinfunction "2_2") (pintype "passive"))
      (node (ref "R2") (pin "2") (pinfunction "2_2") (pintype "passive"))
      (node (ref "R20") (pin "2") (pinfunction "2_2") (pintype "passive"))
      (node (ref "R21") (pin "2") (pinfunction "2_2") (pintype "passive"))
      (node (ref "R22") (pin "2") (pinfunction "2_2") (pintype "passive"))
      (node (ref "R23") (pin "2") (pinfunction "2_2") (pintype "passive"))
      (node (ref "R3") (pin "2") (pinfunction "2_2") (pintype "passive"))
      (node (ref "R4") (pin "2") (pinfunction "2_2") (pintype "passive"))
      (node (ref "R5") (pin "2") (pinfunction "2_2") (pintype "passive"))
      (node (ref "R6") (pin "2") (pinfunction "2_2") (pintype "passive"))
      (node (ref "R7") (pin "2") (pinfunction "2_2") (pintype "passive"))
      (node (ref "R8") (pin "2") (pinfunction "2_2") (pintype "passive"))
      (node (ref "R9") (pin "2") (pinfunction "2_2") (pintype "passive"))
    )
    (net (code "54") (name "1P5V") (class "Default")
      (node (ref "C10") (pin "2") (pinfunction "2_2") (pintype "passive"))
      (node (ref "C15") (pin "2") (pinfunction "2_2") (pintype "passive"))
      (node (ref "C16") (pin "2") (pinfunction "2_2") (pintype "passive"))
      (node (ref "C17") (pin "2") (pinfunction "2_2") (pintype "passive"))
      (node (ref "C18") (pin "2") (pinfunction "2_2") (pintype "passive"))
      (node (ref "C19") (pin "2") (pinfunction "2_2") (pintype "passive"))
      (node (ref "C20") (pin "2") (pinfunction "2_2") (pintype "passive"))
      (node (ref "C21") (pin "2") (pinfunction "2_2") (pintype "passive"))
      (node (ref "C22") (pin "2") (pinfunction "2_2") (pintype "passive"))
      (node (ref "C3") (pin "2") (pinfunction "2_2") (pintype "passive"))
      (node (ref "C4") (pin "2") (pinfunction "2_2") (pintype "passive"))
      (node (ref "C5") (pin "2") (pinfunction "2_2") (pintype "passive"))
      (node (ref "C6") (pin "2") (pinfunction "2_2") (pintype "passive"))
      (node (ref "C7") (pin "2") (pinfunction "2_2") (pintype "passive"))
      (node (ref "C8") (pin "2") (pinfunction "2_2") (pintype "passive"))
      (node (ref "C9") (pin "2") (pinfunction "2_2") (pintype "passive"))
      (node (ref "U1") (pin "A1") (pinfunction "VDDQ_A1") (pintype "power_in"))
      (node (ref "U1") (pin "A8") (pinfunction "VDDQ_A8") (pintype "power_in"))
      (node (ref "U1") (pin "B2") (pinfunction "VDD_B2") (pintype "power_in"))
      (node (ref "U1") (pin "C1") (pinfunction "VDDQ_C1") (pintype "power_in"))
      (node (ref "U1") (pin "C9") (pinfunction "VDDQ_C9") (pintype "power_in"))
      (node (ref "U1") (pin "D2") (pinfunction "VDDQ_D2") (pintype "power_in"))
      (node (ref "U1") (pin "D9") (pinfunction "VDD_D9") (pintype "power_in"))
      (node (ref "U1") (pin "E9") (pinfunction "VDDQ_E9") (pintype "power_in"))
      (node (ref "U1") (pin "F1") (pinfunction "VDDQ_F1") (pintype "power_in"))
      (node (ref "U1") (pin "G7") (pinfunction "VDD_G7") (pintype "power_in"))
      (node (ref "U1") (pin "H2") (pinfunction "VDDQ_H2") (pintype "power_in"))
      (node (ref "U1") (pin "H9") (pinfunction "VDDQ_H9") (pintype "power_in"))
      (node (ref "U1") (pin "K2") (pinfunction "VDD_K2") (pintype "power_in"))
      (node (ref "U1") (pin "K8") (pinfunction "VDD_K8") (pintype "power_in"))
      (node (ref "U1") (pin "N1") (pinfunction "VDD_N1") (pintype "power_in"))
      (node (ref "U1") (pin "N9") (pinfunction "VDD_N9") (pintype "power_in"))
      (node (ref "U1") (pin "R1") (pinfunction "VDD_R1") (pintype "power_in"))
      (node (ref "U1") (pin "R9") (pinfunction "VDD_R9") (pintype "power_in"))
    )
    (net (code "55") (name "GND") (class "Default")
      (node (ref "C1") (pin "1") (pinfunction "1_1") (pintype "passive"))
      (node (ref "C10") (pin "1") (pinfunction "1_1") (pintype "passive"))
      (node (ref "C11") (pin "2") (pinfunction "2_2") (pintype "passive"))
      (node (ref "C12") (pin "2") (pinfunction "2_2") (pintype "passive"))
      (node (ref "C13") (pin "1") (pinfunction "1_1") (pintype "passive"))
      (node (ref "C14") (pin "1") (pinfunction "1_1") (pintype "passive"))
      (node (ref "C15") (pin "1") (pinfunction "1_1") (pintype "passive"))
      (node (ref "C16") (pin "1") (pinfunction "1_1") (pintype "passive"))
      (node (ref "C17") (pin "1") (pinfunction "1_1") (pintype "passive"))
      (node (ref "C18") (pin "1") (pinfunction "1_1") (pintype "passive"))
      (node (ref "C19") (pin "1") (pinfunction "1_1") (pintype "passive"))
      (node (ref "C2") (pin "1") (pinfunction "1_1") (pintype "passive"))
      (node (ref "C20") (pin "1") (pinfunction "1_1") (pintype "passive"))
      (node (ref "C21") (pin "1") (pinfunction "1_1") (pintype "passive"))
      (node (ref "C22") (pin "1") (pinfunction "1_1") (pintype "passive"))
      (node (ref "C23") (pin "1") (pinfunction "1_1") (pintype "passive"))
      (node (ref "C24") (pin "1") (pinfunction "1_1") (pintype "passive"))
      (node (ref "C25") (pin "1") (pinfunction "1_1") (pintype "passive"))
      (node (ref "C26") (pin "1") (pinfunction "1_1") (pintype "passive"))
      (node (ref "C27") (pin "1") (pinfunction "1_1") (pintype "passive"))
      (node (ref "C28") (pin "1") (pinfunction "1_1") (pintype "passive"))
      (node (ref "C29") (pin "1") (pinfunction "1_1") (pintype "passive"))
      (node (ref "C3") (pin "1") (pinfunction "1_1") (pintype "passive"))
      (node (ref "C30") (pin "1") (pinfunction "1_1") (pintype "passive"))
      (node (ref "C4") (pin "1") (pinfunction "1_1") (pintype "passive"))
      (node (ref "C5") (pin "1") (pinfunction "1_1") (pintype "passive"))
      (node (ref "C6") (pin "1") (pinfunction "1_1") (pintype "passive"))
      (node (ref "C7") (pin "1") (pinfunction "1_1") (pintype "passive"))
      (node (ref "C8") (pin "1") (pinfunction "1_1") (pintype "passive"))
      (node (ref "C9") (pin "1") (pinfunction "1_1") (pintype "passive"))
      (node (ref "R24") (pin "1") (pinfunction "1_1") (pintype "passive"))
      (node (ref "R25") (pin "1") (pinfunction "1_1") (pintype "passive"))
      (node (ref "R26") (pin "1") (pinfunction "1_1") (pintype "passive"))
      (node (ref "U1") (pin "A9") (pinfunction "VSS_A9") (pintype "passive"))
      (node (ref "U1") (pin "B1") (pinfunction "VSSQ_B1") (pintype "passive"))
      (node (ref "U1") (pin "B3") (pinfunction "VSS_B3") (pintype "passive"))
      (node (ref "U1") (pin "B9") (pinfunction "VSSQ_B9") (pintype "passive"))
      (node (ref "U1") (pin "D1") (pinfunction "VSSQ_D1") (pintype "passive"))
      (node (ref "U1") (pin "D8") (pinfunction "VSSQ_D8") (pintype "passive"))
      (node (ref "U1") (pin "E1") (pinfunction "VSS_E1") (pintype "passive"))
      (node (ref "U1") (pin "E2") (pinfunction "VSSQ_E2") (pintype "passive"))
      (node (ref "U1") (pin "E8") (pinfunction "VSSQ_E8") (pintype "passive"))
      (node (ref "U1") (pin "F9") (pinfunction "VSSQ_F9") (pintype "passive"))
      (node (ref "U1") (pin "G1") (pinfunction "VSSQ_G1") (pintype "passive"))
      (node (ref "U1") (pin "G8") (pinfunction "VSS_G8") (pintype "passive"))
      (node (ref "U1") (pin "G9") (pinfunction "VSSQ_G9") (pintype "passive"))
      (node (ref "U1") (pin "J2") (pinfunction "VSS_J2") (pintype "passive"))
      (node (ref "U1") (pin "J8") (pinfunction "VSS_J8") (pintype "passive"))
      (node (ref "U1") (pin "L2") (pinfunction "CS_L2") (pintype "passive"))
      (node (ref "U1") (pin "M1") (pinfunction "VSS_M1") (pintype "passive"))
      (node (ref "U1") (pin "M9") (pinfunction "VSS_M9") (pintype "passive"))
      (node (ref "U1") (pin "P1") (pinfunction "VSS_P1") (pintype "passive"))
      (node (ref "U1") (pin "P9") (pinfunction "VSS_P9") (pintype "passive"))
      (node (ref "U1") (pin "T1") (pinfunction "VSS_T1") (pintype "passive"))
      (node (ref "U1") (pin "T9") (pinfunction "VSS_T9") (pintype "passive"))
    )
    (net (code "56") (name "Net-(U1-ZQ)") (class "Default")
      (node (ref "R24") (pin "2") (pinfunction "2_2") (pintype "passive"))
      (node (ref "U1") (pin "L8") (pinfunction "ZQ_L8") (pintype "passive"))
    )
    (net (code "57") (name "VREF_0V75") (class "Default")
      (node (ref "C1") (pin "2") (pinfunction "2_2") (pintype "passive"))
      (node (ref "C2") (pin "2") (pinfunction "2_2") (pintype "passive"))
      (node (ref "U1") (pin "H1") (pinfunction "VREFDQ_H1") (pintype "passive"))
      (node (ref "U1") (pin "M8") (pinfunction "VREFCA_M8") (pintype "passive"))
    )
    (net (code "58") (name "unconnected-(U1-NC-PadJ1)") (class "Default")
      (node (ref "U1") (pin "J1") (pinfunction "NC_J1") (pintype "passive+no_connect"))
    )
    (net (code "59") (name "unconnected-(U1-NC-PadJ9)") (class "Default")
      (node (ref "U1") (pin "J9") (pinfunction "NC_J9") (pintype "passive+no_connect"))
    )
    (net (code "60") (name "unconnected-(U1-NC-PadL1)") (class "Default")
      (node (ref "U1") (pin "L1") (pinfunction "NC_L1") (pintype "passive+no_connect"))
    )
    (net (code "61") (name "unconnected-(U1-NC-PadL9)") (class "Default")
      (node (ref "U1") (pin "L9") (pinfunction "NC_L9") (pintype "passive+no_connect"))
    )
    (net (code "62") (name "unconnected-(U1-NC-PadM7)") (class "Default")
      (node (ref "U1") (pin "M7") (pinfunction "NC_M7") (pintype "passive+no_connect"))
    )
    (net (code "63") (name "unconnected-(U1-NC-PadT7)") (class "Default")
      (node (ref "U1") (pin "T7") (pinfunction "NC_T7") (pintype "passive+no_connect"))
    )
  )
)
